# LedModulePower.net
KiCad netlist of a schematic drawn in Altium Designer
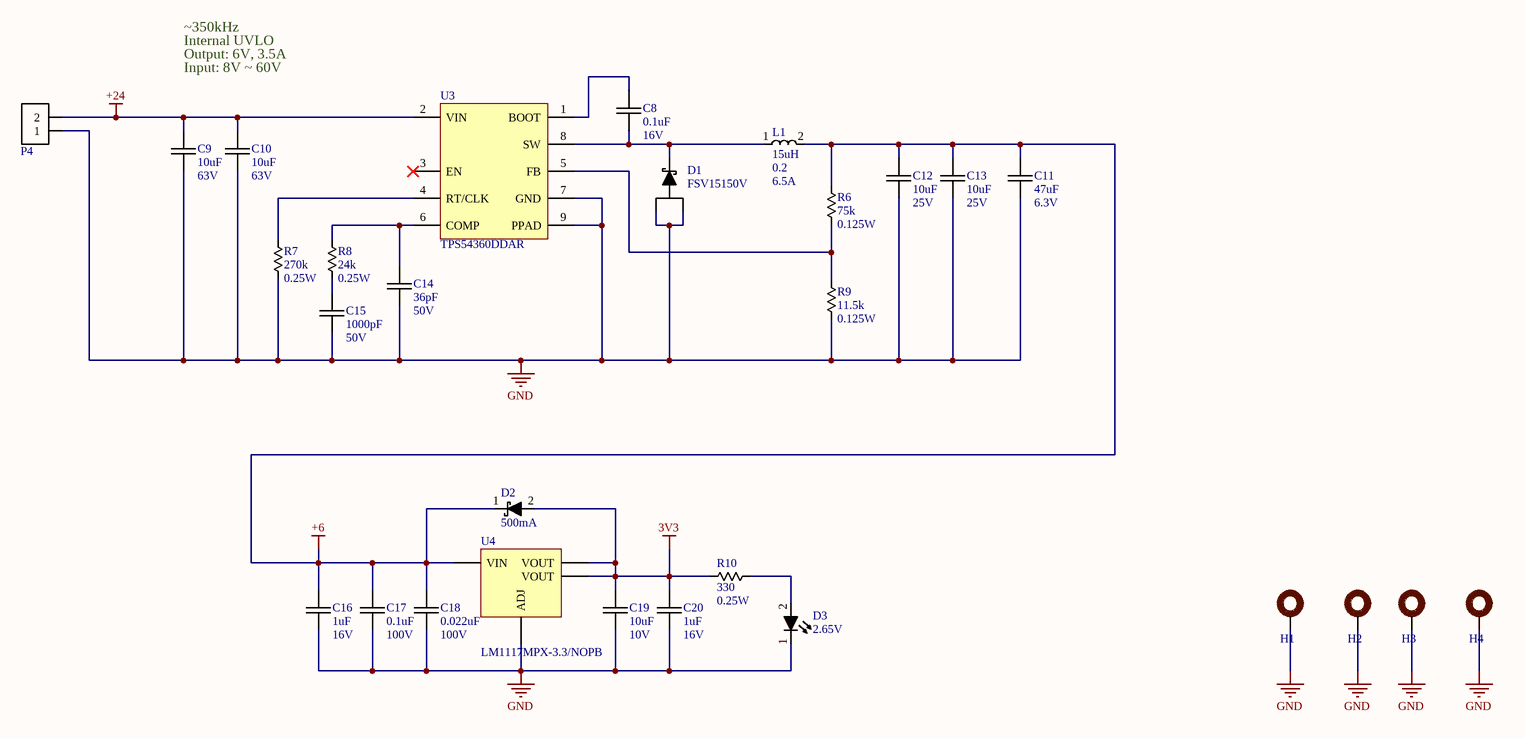
[diagram p0: LedModulePower.SchDoc]

(export (version "E")
  (design (tool "Eeschema 10.0.6"))
  (components
    (comp (ref "C8")
      (value "cap_single_np")
      (footprint "chip_0603")
      (description "CAP, 0.1uF, ±10%, 16V, X7R, 0603")
      (fields
        (field (name "TOLERANCE") "±10%")
        (field (name "CAPACITANCE") "0.1uF")
        (field (name "VOLTAGE RATING") "16V")
        (field (name "PART NUMBER") "CAP-00542")
      )
      (libsource (lib "Capacitors") (part "cap_single_np"))
    )
    (comp (ref "C9")
      (value "cap_single_np")
      (footprint "chip_1210")
      (description "CAP, 10uF, ±10%, 63V, X7R, 1210")
      (fields
        (field (name "TOLERANCE") "±10%")
        (field (name "CAPACITANCE") "10uF")
        (field (name "VOLTAGE RATING") "63V")
        (field (name "PART NUMBER") "CAP-00554")
      )
      (libsource (lib "Capacitors") (part "cap_single_np"))
    )
    (comp (ref "C10")
      (value "cap_single_np")
      (footprint "chip_1210")
      (description "CAP, 10uF, ±10%, 63V, X7R, 1210")
      (fields
        (field (name "TOLERANCE") "±10%")
        (field (name "CAPACITANCE") "10uF")
        (field (name "VOLTAGE RATING") "63V")
        (field (name "PART NUMBER") "CAP-00554")
      )
      (libsource (lib "Capacitors") (part "cap_single_np"))
    )
    (comp (ref "C11")
      (value "cap_single_np")
      (footprint "chip_1210")
      (description "CAP, 47uF, ±20%, 6.3V, X7R, 1210")
      (fields
        (field (name "TOLERANCE") "±20%")
        (field (name "CAPACITANCE") "47uF")
        (field (name "VOLTAGE RATING") "6.3V")
        (field (name "PART NUMBER") "CAP-00557")
      )
      (libsource (lib "Capacitors") (part "cap_single_np"))
    )
    (comp (ref "C12")
      (value "cap_single_np")
      (footprint "chip_1206")
      (description "CAP, 10uF, ±10%, 25V, X7R, 1206")
      (fields
        (field (name "TOLERANCE") "±10%")
        (field (name "CAPACITANCE") "10uF")
        (field (name "VOLTAGE RATING") "25V")
        (field (name "PART NUMBER") "CAP-00539")
      )
      (libsource (lib "Capacitors") (part "cap_single_np"))
    )
    (comp (ref "C13")
      (value "cap_single_np")
      (footprint "chip_1206")
      (description "CAP, 10uF, ±10%, 25V, X7R, 1206")
      (fields
        (field (name "TOLERANCE") "±10%")
        (field (name "CAPACITANCE") "10uF")
        (field (name "VOLTAGE RATING") "25V")
        (field (name "PART NUMBER") "CAP-00539")
      )
      (libsource (lib "Capacitors") (part "cap_single_np"))
    )
    (comp (ref "C14")
      (value "cap_single_np")
      (footprint "chip_0603")
      (description "CAP, 36pF, ±2%, 50V, C0G, 0603")
      (fields
        (field (name "TOLERANCE") "±2%")
        (field (name "CAPACITANCE") "36pF")
        (field (name "VOLTAGE RATING") "50V")
        (field (name "PART NUMBER") "CAP-00452")
      )
      (libsource (lib "Capacitors") (part "cap_single_np"))
    )
    (comp (ref "C15")
      (value "cap_single_np")
      (footprint "chip_0603")
      (description "CAP, 1000pF, ±2%, 50V, C0G, 0603")
      (fields
        (field (name "TOLERANCE") "±2%")
        (field (name "CAPACITANCE") "1000pF")
        (field (name "VOLTAGE RATING") "50V")
        (field (name "PART NUMBER") "CAP-00465")
      )
      (libsource (lib "Capacitors") (part "cap_single_np"))
    )
    (comp (ref "C16")
      (value "cap_single_np")
      (footprint "chip_0805")
      (description "CAP, 1uF, 10%, 16V, X7R, 0805")
      (fields
        (field (name "TOLERANCE") "10%")
        (field (name "CAPACITANCE") "1uF")
        (field (name "VOLTAGE RATING") "16V")
        (field (name "PART NUMBER") "CAP-00107")
      )
      (libsource (lib "Capacitors") (part "cap_single_np"))
    )
    (comp (ref "C17")
      (value "cap_single_np")
      (footprint "chip_0603")
      (description "CAP, 0.1uF, ±10%, 100V, X7R, 0603")
      (fields
        (field (name "TOLERANCE") "±10%")
        (field (name "CAPACITANCE") "0.1uF")
        (field (name "VOLTAGE RATING") "100V")
        (field (name "PART NUMBER") "CAP-00530")
      )
      (libsource (lib "Capacitors") (part "cap_single_np"))
    )
    (comp (ref "C18")
      (value "cap_single_np")
      (footprint "chip_0603")
      (description "CAP, 0.022uF, ±10%, 100V, X7R, 0603")
      (fields
        (field (name "TOLERANCE") "±10%")
        (field (name "CAPACITANCE") "0.022uF")
        (field (name "VOLTAGE RATING") "100V")
        (field (name "PART NUMBER") "CAP-00524")
      )
      (libsource (lib "Capacitors") (part "cap_single_np"))
    )
    (comp (ref "C19")
      (value "cap_single_np")
      (footprint "chip_0805")
      (description "CAP, 10uF, 10%, 10V, X7R, 0805")
      (fields
        (field (name "TOLERANCE") "10%")
        (field (name "CAPACITANCE") "10uF")
        (field (name "VOLTAGE RATING") "10V")
        (field (name "PART NUMBER") "CAP-00131")
      )
      (libsource (lib "Capacitors") (part "cap_single_np"))
    )
    (comp (ref "C20")
      (value "cap_single_np")
      (footprint "chip_0805")
      (description "CAP, 1uF, 10%, 16V, X7R, 0805")
      (fields
        (field (name "TOLERANCE") "10%")
        (field (name "CAPACITANCE") "1uF")
        (field (name "VOLTAGE RATING") "16V")
        (field (name "PART NUMBER") "CAP-00107")
      )
      (libsource (lib "Capacitors") (part "cap_single_np"))
    )
    (comp (ref "D1")
      (value "diode_sch_A12C3")
      (footprint "TO-277-3")
      (description "Dio, Schottky, 15A, 0.85V, 150V, TO-227")
      (fields
        (field (name "MANUFACTURER PN") "FSV15150V")
        (field (name "PART NUMBER") "DIO-00054")
        (field (name "MANUFACTURER") "ON Semi")
      )
      (libsource (lib "Diodes") (part "diode_sch_A12C3"))
    )
    (comp (ref "D2")
      (value "diode_2")
      (footprint "sod323_0")
      (description "Dio Shtky, 500mA, 0.62V, 30V, SOD-323")
      (fields
        (field (name "CURRENT RATING") "500mA")
        (field (name "PART NUMBER") "DIO-00000")
        (field (name "MANUFACTURER") "ON Semi")
      )
      (libsource (lib "Diodes") (part "diode_2"))
    )
    (comp (ref "D3")
      (value "diode_4")
      (footprint "chip_0603")
      (description "LED, Blue, 0603, Low current, HELI2 Series")
      (fields
        (field (name "FORWARD VOLTAGE") "2.65V")
        (field (name "PART NUMBER") "DIO-00049")
        (field (name "MANUFACTURER") "Kingbright")
      )
      (libsource (lib "Diodes") (part "diode_4"))
    )
    (comp (ref "H1")
      (value "mounting_hole_0")
      (footprint "#8-32_SOCKET_HEAD")
      (description "#8-32 Mounting Hole for Socket Head Cap Screw")
      (fields (field (name "PART NUMBER") "MISC-00027"))
      (libsource (lib "Misc") (part "mounting_hole_0"))
    )
    (comp (ref "H2")
      (value "mounting_hole_0")
      (footprint "#8-32_SOCKET_HEAD")
      (description "#8-32 Mounting Hole for Socket Head Cap Screw")
      (fields (field (name "PART NUMBER") "MISC-00027"))
      (libsource (lib "Misc") (part "mounting_hole_0"))
    )
    (comp (ref "H3")
      (value "mounting_hole_0")
      (footprint "#8-32_SOCKET_HEAD")
      (description "#8-32 Mounting Hole for Socket Head Cap Screw")
      (fields (field (name "PART NUMBER") "MISC-00027"))
      (libsource (lib "Misc") (part "mounting_hole_0"))
    )
    (comp (ref "H4")
      (value "mounting_hole_0")
      (footprint "#8-32_SOCKET_HEAD")
      (description "#8-32 Mounting Hole for Socket Head Cap Screw")
      (fields (field (name "PART NUMBER") "MISC-00027"))
      (libsource (lib "Misc") (part "mounting_hole_0"))
    )
    (comp (ref "L1")
      (value "ind_0")
      (footprint "7447709150")
      (description "Ind, 15uH, 0.2, 6.5A, 7447709150")
      (fields
        (field (name "INDUCTANCE") "15uH")
        (field (name "TOLERANCE") "0.2")
        (field (name "CURRENT RATING") "6.5A")
        (field (name "PART NUMBER") "MAG-00090")
        (field (name "MANUFACTURER") "Wurth")
      )
      (libsource (lib "Magnetics") (part "ind_0"))
    )
    (comp (ref "P4")
      (value "conn-2x1_0")
      (footprint "TERM_3.50MM_2x1_0")
      (description "Term Blk, 2 Pos, 16A, 3.5mm Pitch")
      (fields (field (name "PART NUMBER") "CONN-00023") (field (name "MANUFACTURER") "Phoenix Contact"))
      (libsource (lib "Connectors") (part "conn-2x1_0"))
    )
    (comp (ref "R6")
      (value "res_single")
      (footprint "chip_0805")
      (description "RES SMD 75K OHM 1% 1/8W 0805")
      (fields
        (field (name "TOLERANCE") "1%")
        (field (name "RESISTANCE") "75k")
        (field (name "POWER RATING") "0.125W")
        (field (name "PART NUMBER") "RES-00554")
      )
      (libsource (lib "Resistors") (part "res_single"))
    )
    (comp (ref "R7")
      (value "res_single")
      (footprint "chip_0603")
      (description "RES SMD 270K OHM 1% 1/4W 0603")
      (fields
        (field (name "TOLERANCE") "1%")
        (field (name "RESISTANCE") "270k")
        (field (name "POWER RATING") "0.25W")
        (field (name "PART NUMBER") "RES-00405")
      )
      (libsource (lib "Resistors") (part "res_single"))
    )
    (comp (ref "R8")
      (value "res_single")
      (footprint "chip_0603")
      (description "RES SMD 24K OHM 1% 1/4W 0603")
      (fields
        (field (name "TOLERANCE") "1%")
        (field (name "RESISTANCE") "24k")
        (field (name "POWER RATING") "0.25W")
        (field (name "PART NUMBER") "RES-00399")
      )
      (libsource (lib "Resistors") (part "res_single"))
    )
    (comp (ref "R9")
      (value "res_single")
      (footprint "chip_0805")
      (description "RES SMD 11.5K OHM 1% 1/8W 0805")
      (fields
        (field (name "TOLERANCE") "1%")
        (field (name "RESISTANCE") "11.5k")
        (field (name "POWER RATING") "0.125W")
        (field (name "PART NUMBER") "RES-00309")
      )
      (libsource (lib "Resistors") (part "res_single"))
    )
    (comp (ref "R10")
      (value "res_single")
      (footprint "chip_0603")
      (description "RES SMD 330 OHM 1% 1/4W 0603")
      (fields
        (field (name "TOLERANCE") "1%")
        (field (name "RESISTANCE") "330")
        (field (name "POWER RATING") "0.25W")
        (field (name "PART NUMBER") "RES-00221")
      )
      (libsource (lib "Resistors") (part "res_single"))
    )
    (comp (ref "U3")
      (value "TPS54360")
      (footprint "SO-8_PPAD")
      (description "REG, SW Buck Adj, 3.5A, 4.5-60V, 2.5MHz")
      (fields
        (field (name "MANUFACTURER PN") "TPS54360DDAR")
        (field (name "PART NUMBER") "PWREG-00017")
        (field (name "MANUFACTURER") "TI")
      )
      (libsource (lib "Power Reg") (part "TPS54360"))
    )
    (comp (ref "U4")
      (value "LM1117")
      (footprint "sot-223-4")
      (description "REG, Linear, Fixed 3V3, 800mA, SOT-223")
      (fields
        (field (name "MANUFACTURER PN") "LM1117MPX-3.3/NOPB")
        (field (name "PART NUMBER") "PWREG-00018")
        (field (name "MANUFACTURER") "TI")
      )
      (libsource (lib "Power Reg") (part "LM1117"))
    )
  )
  (nets
    (net (code "1") (name "+6") (class "Default")
      (node (ref "C11") (pin "1") (pinfunction "1_1") (pintype "passive"))
      (node (ref "C12") (pin "1") (pinfunction "1_1") (pintype "passive"))
      (node (ref "C13") (pin "1") (pinfunction "1_1") (pintype "passive"))
      (node (ref "C16") (pin "1") (pinfunction "1_1") (pintype "passive"))
      (node (ref "C17") (pin "1") (pinfunction "1_1") (pintype "passive"))
      (node (ref "C18") (pin "1") (pinfunction "1_1") (pintype "passive"))
      (node (ref "D2") (pin "1") (pinfunction "1_1") (pintype "passive"))
      (node (ref "L1") (pin "2") (pinfunction "2_2") (pintype "passive"))
      (node (ref "R6") (pin "1") (pinfunction "1_1") (pintype "passive"))
      (node (ref "U4") (pin "3") (pinfunction "VIN_3") (pintype "passive"))
    )
    (net (code "2") (name "+24") (class "Default")
      (node (ref "C10") (pin "1") (pinfunction "1_1") (pintype "passive"))
      (node (ref "C9") (pin "1") (pinfunction "1_1") (pintype "passive"))
      (node (ref "P4") (pin "2") (pinfunction "2_2") (pintype "passive"))
      (node (ref "U3") (pin "2") (pinfunction "VIN_2") (pintype "passive"))
    )
    (net (code "3") (name "3V3") (class "Default")
      (node (ref "C19") (pin "1") (pinfunction "1_1") (pintype "passive"))
      (node (ref "C20") (pin "1") (pinfunction "1_1") (pintype "passive"))
      (node (ref "D2") (pin "2") (pinfunction "2_2") (pintype "passive"))
      (node (ref "R10") (pin "1") (pinfunction "1_1") (pintype "passive"))
      (node (ref "U4") (pin "2") (pinfunction "VOUT_2") (pintype "passive"))
      (node (ref "U4") (pin "4") (pinfunction "VOUT_4") (pintype "passive"))
    )
    (net (code "4") (name "GND") (class "Default")
      (node (ref "C10") (pin "2") (pinfunction "2_2") (pintype "passive"))
      (node (ref "C11") (pin "2") (pinfunction "2_2") (pintype "passive"))
      (node (ref "C12") (pin "2") (pinfunction "2_2") (pintype "passive"))
      (node (ref "C13") (pin "2") (pinfunction "2_2") (pintype "passive"))
      (node (ref "C14") (pin "2") (pinfunction "2_2") (pintype "passive"))
      (node (ref "C15") (pin "2") (pinfunction "2_2") (pintype "passive"))
      (node (ref "C16") (pin "2") (pinfunction "2_2") (pintype "passive"))
      (node (ref "C17") (pin "2") (pinfunction "2_2") (pintype "passive"))
      (node (ref "C18") (pin "2") (pinfunction "2_2") (pintype "passive"))
      (node (ref "C19") (pin "2") (pinfunction "2_2") (pintype "passive"))
      (node (ref "C20") (pin "2") (pinfunction "2_2") (pintype "passive"))
      (node (ref "C9") (pin "2") (pinfunction "2_2") (pintype "passive"))
      (node (ref "D1") (pin "1") (pinfunction "1_1") (pintype "passive"))
      (node (ref "D1") (pin "2") (pinfunction "2_2") (pintype "passive"))
      (node (ref "D3") (pin "1") (pinfunction "1_1") (pintype "passive"))
      (node (ref "H1") (pin "0") (pinfunction "A_0") (pintype "passive"))
      (node (ref "H2") (pin "0") (pinfunction "A_0") (pintype "passive"))
      (node (ref "H3") (pin "0") (pinfunction "A_0") (pintype "passive"))
      (node (ref "H4") (pin "0") (pinfunction "A_0") (pintype "passive"))
      (node (ref "P4") (pin "1") (pinfunction "1_1") (pintype "passive"))
      (node (ref "R7") (pin "2") (pinfunction "2_2") (pintype "passive"))
      (node (ref "R9") (pin "2") (pinfunction "2_2") (pintype "passive"))
      (node (ref "U3") (pin "7") (pinfunction "GND_7") (pintype "passive"))
      (node (ref "U3") (pin "9") (pinfunction "PPAD_9") (pintype "passive"))
      (node (ref "U4") (pin "1") (pinfunction "ADJ_1") (pintype "passive"))
    )
    (net (code "5") (name "Net-(C15-Pad1)") (class "Default")
      (node (ref "C15") (pin "1") (pinfunction "1_1") (pintype "passive"))
      (node (ref "R8") (pin "2") (pinfunction "2_2") (pintype "passive"))
    )
    (net (code "6") (name "Net-(D3-Pad2)") (class "Default")
      (node (ref "D3") (pin "2") (pinfunction "2_2") (pintype "passive"))
      (node (ref "R10") (pin "2") (pinfunction "2_2") (pintype "passive"))
    )
    (net (code "7") (name "Net-(U3-BOOT)") (class "Default")
      (node (ref "C8") (pin "1") (pinfunction "1_1") (pintype "passive"))
      (node (ref "U3") (pin "1") (pinfunction "BOOT_1") (pintype "passive"))
    )
    (net (code "8") (name "Net-(U3-COMP)") (class "Default")
      (node (ref "C14") (pin "1") (pinfunction "1_1") (pintype "passive"))
      (node (ref "R8") (pin "1") (pinfunction "1_1") (pintype "passive"))
      (node (ref "U3") (pin "6") (pinfunction "COMP_6") (pintype "passive"))
    )
    (net (code "9") (name "Net-(U3-FB)") (class "Default")
      (node (ref "R6") (pin "2") (pinfunction "2_2") (pintype "passive"))
      (node (ref "R9") (pin "1") (pinfunction "1_1") (pintype "passive"))
      (node (ref "U3") (pin "5") (pinfunction "FB_5") (pintype "passive"))
    )
    (net (code "10") (name "Net-(U3-RT{slash}CLK)") (class "Default")
      (node (ref "R7") (pin "1") (pinfunction "1_1") (pintype "passive"))
      (node (ref "U3") (pin "4") (pinfunction "RT/CLK_4") (pintype "passive"))
    )
    (net (code "11") (name "Net-(U3-SW)") (class "Default")
      (node (ref "C8") (pin "2") (pinfunction "2_2") (pintype "passive"))
      (node (ref "D1") (pin "3") (pinfunction "3_3") (pintype "passive"))
      (node (ref "L1") (pin "1") (pinfunction "1_1") (pintype "passive"))
      (node (ref "U3") (pin "8") (pinfunction "SW_8") (pintype "passive"))
    )
    (net (code "12") (name "unconnected-(U3-EN-Pad3)") (class "Default")
      (node (ref "U3") (pin "3") (pinfunction "EN_3") (pintype "passive+no_connect"))
    )
  )
)
